# Pontos_Cegos.net
KiCad netlist of a schematic drawn in EAGLE
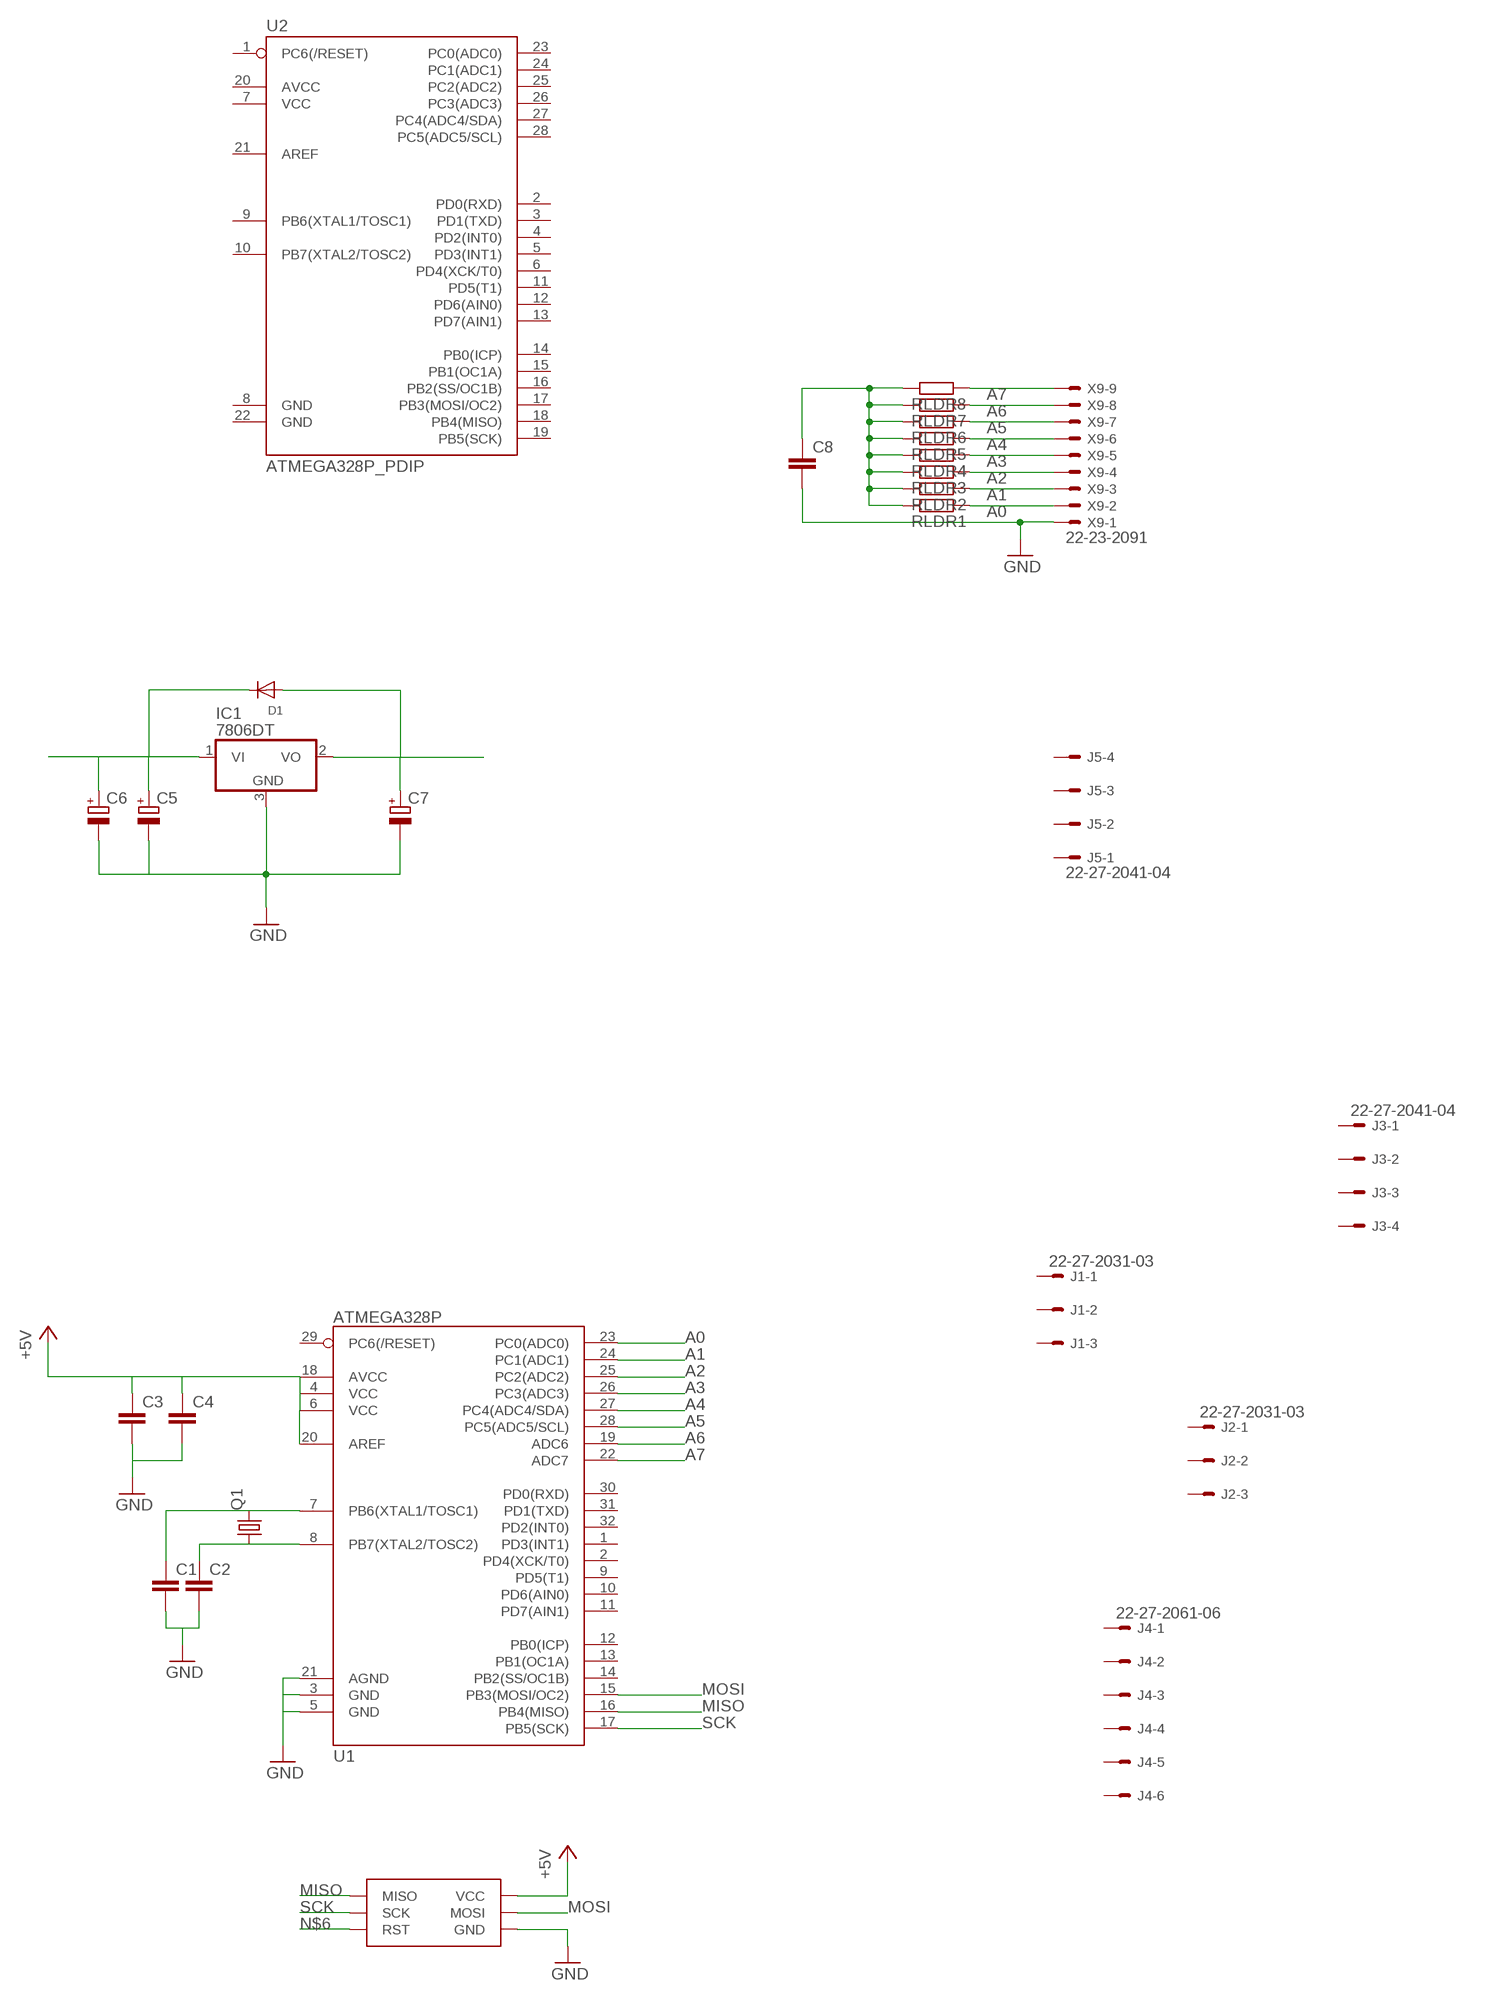
[diagram p0: schematic, sheet 1]

(export (version "E")
  (design (tool "Eeschema 10.0.6"))
  (components
    (comp (ref "C1")
      (value "C-EUC0805")
      (footprint "eagle-import:C0805")
      (libsource (lib "eagle-import") (part "C-EUC0805"))
    )
    (comp (ref "C2")
      (value "C-EUC0805")
      (footprint "eagle-import:C0805")
      (libsource (lib "eagle-import") (part "C-EUC0805"))
    )
    (comp (ref "C3")
      (value "C-EUC0805")
      (footprint "eagle-import:C0805")
      (libsource (lib "eagle-import") (part "C-EUC0805"))
    )
    (comp (ref "C4")
      (value "C-EUC0805")
      (footprint "eagle-import:C0805")
      (libsource (lib "eagle-import") (part "C-EUC0805"))
    )
    (comp (ref "C5")
      (value "CPOL-EUD")
      (footprint "eagle-import:PANASONIC_D")
      (libsource (lib "eagle-import") (part "CPOL-EUD"))
    )
    (comp (ref "C6")
      (value "CPOL-EUD")
      (footprint "eagle-import:PANASONIC_D")
      (libsource (lib "eagle-import") (part "CPOL-EUD"))
    )
    (comp (ref "C7")
      (value "CPOL-EUD")
      (footprint "eagle-import:PANASONIC_D")
      (libsource (lib "eagle-import") (part "CPOL-EUD"))
    )
    (comp (ref "C8")
      (value "C-EUC0805")
      (footprint "eagle-import:C0805")
      (libsource (lib "eagle-import") (part "C-EUC0805"))
    )
    (comp (ref "D1")
      (value "DIODESMA")
      (footprint "eagle-import:SMADIODE")
      (libsource (lib "eagle-import") (part "DIODESMA"))
    )
    (comp (ref "IC1")
      (value "7806DT")
      (footprint "eagle-import:TO252")
      (libsource (lib "eagle-import") (part "78DT06"))
    )
    (comp (ref "J1")
      (value "22-27-2031-03")
      (footprint "eagle-import:6410-03")
      (libsource (lib "eagle-import") (part "22-?-0327-2031"))
    )
    (comp (ref "J2")
      (value "22-27-2031-03")
      (footprint "eagle-import:6410-03")
      (libsource (lib "eagle-import") (part "22-?-0327-2031"))
    )
    (comp (ref "J3")
      (value "22-27-2041-04")
      (footprint "eagle-import:6410-04")
      (libsource (lib "eagle-import") (part "22-?-0427-2041"))
    )
    (comp (ref "J4")
      (value "22-27-2061-06")
      (footprint "eagle-import:6410-06")
      (libsource (lib "eagle-import") (part "22-?-0627-2061"))
    )
    (comp (ref "J5")
      (value "22-27-2041-04")
      (footprint "eagle-import:6410-04")
      (libsource (lib "eagle-import") (part "22-?-0427-2041"))
    )
    (comp (ref "Q1")
      (value "CRYSTALHC49U-V")
      (footprint "eagle-import:HC49U-V")
      (libsource (lib "eagle-import") (part "CRYSTALHC49U-V"))
    )
    (comp (ref "RLDR1")
      (value "R-EU_R0603")
      (footprint "eagle-import:R0603")
      (libsource (lib "eagle-import") (part "R-EU_R0603"))
    )
    (comp (ref "RLDR2")
      (value "R-EU_R0603")
      (footprint "eagle-import:R0603")
      (libsource (lib "eagle-import") (part "R-EU_R0603"))
    )
    (comp (ref "RLDR3")
      (value "R-EU_R0603")
      (footprint "eagle-import:R0603")
      (libsource (lib "eagle-import") (part "R-EU_R0603"))
    )
    (comp (ref "RLDR4")
      (value "R-EU_R0603")
      (footprint "eagle-import:R0603")
      (libsource (lib "eagle-import") (part "R-EU_R0603"))
    )
    (comp (ref "RLDR5")
      (value "R-EU_R0603")
      (footprint "eagle-import:R0603")
      (libsource (lib "eagle-import") (part "R-EU_R0603"))
    )
    (comp (ref "RLDR6")
      (value "R-EU_R0603")
      (footprint "eagle-import:R0603")
      (libsource (lib "eagle-import") (part "R-EU_R0603"))
    )
    (comp (ref "RLDR7")
      (value "R-EU_R0603")
      (footprint "eagle-import:R0603")
      (libsource (lib "eagle-import") (part "R-EU_R0603"))
    )
    (comp (ref "RLDR8")
      (value "R-EU_R0603")
      (footprint "eagle-import:R0603")
      (libsource (lib "eagle-import") (part "R-EU_R0603"))
    )
    (comp (ref "U$1")
      (value "ISP_POGOISP_POGO")
      (footprint "eagle-import:ISP_POGO")
      (libsource (lib "eagle-import") (part "ISP_POGOISP_POGO"))
    )
    (comp (ref "U1")
      (value "ATMEGA328P")
      (footprint "eagle-import:TQFP32-08")
      (libsource (lib "eagle-import") (part "ATMEGA328_SMT"))
    )
    (comp (ref "U2")
      (value "ATMEGA328P_PDIP")
      (footprint "eagle-import:DIL28-3")
      (libsource (lib "eagle-import") (part "ATMEGA328P_PDIP"))
    )
    (comp (ref "X9")
      (value "22-23-2091")
      (footprint "eagle-import:22-23-2091")
      (fields (field (name "MF") "MOLEX"))
      (libsource (lib "eagle-import") (part "22-23-2091"))
    )
  )
  (nets
    (net (code "1") (name "+5V") (class "Default")
      (node (ref "C3") (pin "1") (pinfunction "1_1") (pintype "passive"))
      (node (ref "C4") (pin "1") (pinfunction "1_1") (pintype "passive"))
      (node (ref "C8") (pin "1") (pinfunction "1_1") (pintype "passive"))
      (node (ref "RLDR1") (pin "1") (pinfunction "1_1") (pintype "passive"))
      (node (ref "RLDR2") (pin "1") (pinfunction "1_1") (pintype "passive"))
      (node (ref "RLDR3") (pin "1") (pinfunction "1_1") (pintype "passive"))
      (node (ref "RLDR4") (pin "1") (pinfunction "1_1") (pintype "passive"))
      (node (ref "RLDR5") (pin "1") (pinfunction "1_1") (pintype "passive"))
      (node (ref "RLDR6") (pin "1") (pinfunction "1_1") (pintype "passive"))
      (node (ref "RLDR7") (pin "1") (pinfunction "1_1") (pintype "passive"))
      (node (ref "RLDR8") (pin "1") (pinfunction "1_1") (pintype "passive"))
      (node (ref "U$1") (pin "VCC") (pinfunction "VCC_VCC") (pintype "bidirectional"))
      (node (ref "U1") (pin "18") (pinfunction "AVCC_18") (pintype "bidirectional"))
      (node (ref "U1") (pin "20") (pinfunction "AREF_20") (pintype "bidirectional"))
      (node (ref "U1") (pin "4") (pinfunction "VCC_4") (pintype "bidirectional"))
      (node (ref "U1") (pin "6") (pinfunction "VCC_6") (pintype "bidirectional"))
    )
    (net (code "2") (name "/A0") (class "Default")
      (node (ref "RLDR1") (pin "2") (pinfunction "2_2") (pintype "passive"))
      (node (ref "U1") (pin "23") (pinfunction "PC0(ADC0)_23") (pintype "bidirectional"))
      (node (ref "X9") (pin "2") (pinfunction "S_2") (pintype "passive"))
    )
    (net (code "3") (name "/A1") (class "Default")
      (node (ref "RLDR2") (pin "2") (pinfunction "2_2") (pintype "passive"))
      (node (ref "U1") (pin "24") (pinfunction "PC1(ADC1)_24") (pintype "bidirectional"))
      (node (ref "X9") (pin "3") (pinfunction "S_3") (pintype "passive"))
    )
    (net (code "4") (name "/A2") (class "Default")
      (node (ref "RLDR3") (pin "2") (pinfunction "2_2") (pintype "passive"))
      (node (ref "U1") (pin "25") (pinfunction "PC2(ADC2)_25") (pintype "bidirectional"))
      (node (ref "X9") (pin "4") (pinfunction "S_4") (pintype "passive"))
    )
    (net (code "5") (name "/A3") (class "Default")
      (node (ref "RLDR4") (pin "2") (pinfunction "2_2") (pintype "passive"))
      (node (ref "U1") (pin "26") (pinfunction "PC3(ADC3)_26") (pintype "bidirectional"))
      (node (ref "X9") (pin "5") (pinfunction "S_5") (pintype "passive"))
    )
    (net (code "6") (name "/A4") (class "Default")
      (node (ref "RLDR5") (pin "2") (pinfunction "2_2") (pintype "passive"))
      (node (ref "U1") (pin "27") (pinfunction "PC4(ADC4/SDA)_27") (pintype "bidirectional"))
      (node (ref "X9") (pin "6") (pinfunction "S_6") (pintype "passive"))
    )
    (net (code "7") (name "/A5") (class "Default")
      (node (ref "RLDR6") (pin "2") (pinfunction "2_2") (pintype "passive"))
      (node (ref "U1") (pin "28") (pinfunction "PC5(ADC5/SCL)_28") (pintype "bidirectional"))
      (node (ref "X9") (pin "7") (pinfunction "S_7") (pintype "passive"))
    )
    (net (code "8") (name "/A6") (class "Default")
      (node (ref "RLDR7") (pin "2") (pinfunction "2_2") (pintype "passive"))
      (node (ref "U1") (pin "19") (pinfunction "ADC6_19") (pintype "bidirectional"))
      (node (ref "X9") (pin "8") (pinfunction "S_8") (pintype "passive"))
    )
    (net (code "9") (name "/A7") (class "Default")
      (node (ref "RLDR8") (pin "2") (pinfunction "2_2") (pintype "passive"))
      (node (ref "U1") (pin "22") (pinfunction "ADC7_22") (pintype "bidirectional"))
      (node (ref "X9") (pin "9") (pinfunction "S_9") (pintype "passive"))
    )
    (net (code "10") (name "/MISO") (class "Default")
      (node (ref "U$1") (pin "MISO") (pinfunction "MISO_MISO") (pintype "bidirectional"))
      (node (ref "U1") (pin "16") (pinfunction "PB4(MISO)_16") (pintype "bidirectional"))
    )
    (net (code "11") (name "/MOSI") (class "Default")
      (node (ref "U$1") (pin "MOSI") (pinfunction "MOSI_MOSI") (pintype "bidirectional"))
      (node (ref "U1") (pin "15") (pinfunction "PB3(MOSI/OC2)_15") (pintype "bidirectional"))
    )
    (net (code "12") (name "/N$6") (class "Default")
      (node (ref "U$1") (pin "RST") (pinfunction "RST_RST") (pintype "bidirectional"))
    )
    (net (code "13") (name "/SCK") (class "Default")
      (node (ref "U$1") (pin "SCK") (pinfunction "SCK_SCK") (pintype "bidirectional"))
      (node (ref "U1") (pin "17") (pinfunction "PB5(SCK)_17") (pintype "bidirectional"))
    )
    (net (code "14") (name "GND") (class "Default")
      (node (ref "C1") (pin "2") (pinfunction "2_2") (pintype "passive"))
      (node (ref "C2") (pin "2") (pinfunction "2_2") (pintype "passive"))
      (node (ref "C3") (pin "2") (pinfunction "2_2") (pintype "passive"))
      (node (ref "C4") (pin "2") (pinfunction "2_2") (pintype "passive"))
      (node (ref "C5") (pin "-") (pinfunction "-_-") (pintype "passive"))
      (node (ref "C6") (pin "-") (pinfunction "-_-") (pintype "passive"))
      (node (ref "C7") (pin "-") (pinfunction "-_-") (pintype "passive"))
      (node (ref "C8") (pin "2") (pinfunction "2_2") (pintype "passive"))
      (node (ref "IC1") (pin "3") (pinfunction "GND_3") (pintype "passive"))
      (node (ref "U$1") (pin "GND") (pinfunction "GND_GND") (pintype "bidirectional"))
      (node (ref "U1") (pin "21") (pinfunction "AGND_21") (pintype "bidirectional"))
      (node (ref "U1") (pin "3") (pinfunction "GND_3") (pintype "bidirectional"))
      (node (ref "U1") (pin "5") (pinfunction "GND_5") (pintype "bidirectional"))
      (node (ref "X9") (pin "1") (pinfunction "S_1") (pintype "passive"))
    )
    (net (code "15") (name "Net-(IC1-VI)") (class "Default")
      (node (ref "C5") (pin "+") (pinfunction "+_+") (pintype "passive"))
      (node (ref "C6") (pin "+") (pinfunction "+_+") (pintype "passive"))
      (node (ref "D1") (pin "C") (pinfunction "C_C") (pintype "passive"))
      (node (ref "IC1") (pin "1") (pinfunction "VI_1") (pintype "input"))
    )
    (net (code "16") (name "Net-(IC1-VO)") (class "Default")
      (node (ref "C7") (pin "+") (pinfunction "+_+") (pintype "passive"))
      (node (ref "D1") (pin "A") (pinfunction "A_A") (pintype "passive"))
      (node (ref "IC1") (pin "2") (pinfunction "VO_2") (pintype "passive"))
    )
    (net (code "17") (name "Net-(U1-PB6(XTAL1{slash}TOSC1))") (class "Default")
      (node (ref "C1") (pin "1") (pinfunction "1_1") (pintype "passive"))
      (node (ref "Q1") (pin "2") (pinfunction "2_2") (pintype "passive"))
      (node (ref "U1") (pin "7") (pinfunction "PB6(XTAL1/TOSC1)_7") (pintype "bidirectional"))
    )
    (net (code "18") (name "Net-(U1-PB7(XTAL2{slash}TOSC2))") (class "Default")
      (node (ref "C2") (pin "1") (pinfunction "1_1") (pintype "passive"))
      (node (ref "Q1") (pin "1") (pinfunction "1_1") (pintype "passive"))
      (node (ref "U1") (pin "8") (pinfunction "PB7(XTAL2/TOSC2)_8") (pintype "bidirectional"))
    )
    (net (code "19") (name "unconnected-(J1A-S-Pad1)") (class "Default")
      (node (ref "J1") (pin "1") (pinfunction "S_1") (pintype "passive"))
    )
    (net (code "20") (name "unconnected-(J1B-S-Pad2)") (class "Default")
      (node (ref "J1") (pin "2") (pinfunction "S_2") (pintype "passive"))
    )
    (net (code "21") (name "unconnected-(J1C-S-Pad3)") (class "Default")
      (node (ref "J1") (pin "3") (pinfunction "S_3") (pintype "passive"))
    )
    (net (code "22") (name "unconnected-(J2A-S-Pad1)") (class "Default")
      (node (ref "J2") (pin "1") (pinfunction "S_1") (pintype "passive"))
    )
    (net (code "23") (name "unconnected-(J2B-S-Pad2)") (class "Default")
      (node (ref "J2") (pin "2") (pinfunction "S_2") (pintype "passive"))
    )
    (net (code "24") (name "unconnected-(J2C-S-Pad3)") (class "Default")
      (node (ref "J2") (pin "3") (pinfunction "S_3") (pintype "passive"))
    )
    (net (code "25") (name "unconnected-(J3A-S-Pad1)") (class "Default")
      (node (ref "J3") (pin "1") (pinfunction "S_1") (pintype "passive"))
    )
    (net (code "26") (name "unconnected-(J3B-S-Pad2)") (class "Default")
      (node (ref "J3") (pin "2") (pinfunction "S_2") (pintype "passive"))
    )
    (net (code "27") (name "unconnected-(J3C-S-Pad3)") (class "Default")
      (node (ref "J3") (pin "3") (pinfunction "S_3") (pintype "passive"))
    )
    (net (code "28") (name "unconnected-(J3D-S-Pad4)") (class "Default")
      (node (ref "J3") (pin "4") (pinfunction "S_4") (pintype "passive"))
    )
    (net (code "29") (name "unconnected-(J4A-S-Pad1)") (class "Default")
      (node (ref "J4") (pin "1") (pinfunction "S_1") (pintype "passive"))
    )
    (net (code "30") (name "unconnected-(J4B-S-Pad2)") (class "Default")
      (node (ref "J4") (pin "2") (pinfunction "S_2") (pintype "passive"))
    )
    (net (code "31") (name "unconnected-(J4C-S-Pad3)") (class "Default")
      (node (ref "J4") (pin "3") (pinfunction "S_3") (pintype "passive"))
    )
    (net (code "32") (name "unconnected-(J4D-S-Pad4)") (class "Default")
      (node (ref "J4") (pin "4") (pinfunction "S_4") (pintype "passive"))
    )
    (net (code "33") (name "unconnected-(J4E-S-Pad5)") (class "Default")
      (node (ref "J4") (pin "5") (pinfunction "S_5") (pintype "passive"))
    )
    (net (code "34") (name "unconnected-(J4F-S-Pad6)") (class "Default")
      (node (ref "J4") (pin "6") (pinfunction "S_6") (pintype "passive"))
    )
    (net (code "35") (name "unconnected-(J5A-S-Pad1)") (class "Default")
      (node (ref "J5") (pin "1") (pinfunction "S_1") (pintype "passive"))
    )
    (net (code "36") (name "unconnected-(J5B-S-Pad2)") (class "Default")
      (node (ref "J5") (pin "2") (pinfunction "S_2") (pintype "passive"))
    )
    (net (code "37") (name "unconnected-(J5C-S-Pad3)") (class "Default")
      (node (ref "J5") (pin "3") (pinfunction "S_3") (pintype "passive"))
    )
    (net (code "38") (name "unconnected-(J5D-S-Pad4)") (class "Default")
      (node (ref "J5") (pin "4") (pinfunction "S_4") (pintype "passive"))
    )
    (net (code "39") (name "unconnected-(U1-PB0(ICP)-Pad12)") (class "Default")
      (node (ref "U1") (pin "12") (pinfunction "PB0(ICP)_12") (pintype "bidirectional"))
    )
    (net (code "40") (name "unconnected-(U1-PB1(OC1A)-Pad13)") (class "Default")
      (node (ref "U1") (pin "13") (pinfunction "PB1(OC1A)_13") (pintype "bidirectional"))
    )
    (net (code "41") (name "unconnected-(U1-PB2(SS{slash}OC1B)-Pad14)") (class "Default")
      (node (ref "U1") (pin "14") (pinfunction "PB2(SS/OC1B)_14") (pintype "bidirectional"))
    )
    (net (code "42") (name "unconnected-(U1-PC6({slash}RESET)-Pad29)") (class "Default")
      (node (ref "U1") (pin "29") (pinfunction "PC6(/RESET)_29") (pintype "bidirectional"))
    )
    (net (code "43") (name "unconnected-(U1-PD0(RXD)-Pad30)") (class "Default")
      (node (ref "U1") (pin "30") (pinfunction "PD0(RXD)_30") (pintype "bidirectional"))
    )
    (net (code "44") (name "unconnected-(U1-PD1(TXD)-Pad31)") (class "Default")
      (node (ref "U1") (pin "31") (pinfunction "PD1(TXD)_31") (pintype "bidirectional"))
    )
    (net (code "45") (name "unconnected-(U1-PD2(INT0)-Pad32)") (class "Default")
      (node (ref "U1") (pin "32") (pinfunction "PD2(INT0)_32") (pintype "bidirectional"))
    )
    (net (code "46") (name "unconnected-(U1-PD3(INT1)-Pad1)") (class "Default")
      (node (ref "U1") (pin "1") (pinfunction "PD3(INT1)_1") (pintype "bidirectional"))
    )
    (net (code "47") (name "unconnected-(U1-PD4(XCK{slash}T0)-Pad2)") (class "Default")
      (node (ref "U1") (pin "2") (pinfunction "PD4(XCK/T0)_2") (pintype "bidirectional"))
    )
    (net (code "48") (name "unconnected-(U1-PD5(T1)-Pad9)") (class "Default")
      (node (ref "U1") (pin "9") (pinfunction "PD5(T1)_9") (pintype "bidirectional"))
    )
    (net (code "49") (name "unconnected-(U1-PD6(AIN0)-Pad10)") (class "Default")
      (node (ref "U1") (pin "10") (pinfunction "PD6(AIN0)_10") (pintype "bidirectional"))
    )
    (net (code "50") (name "unconnected-(U1-PD7(AIN1)-Pad11)") (class "Default")
      (node (ref "U1") (pin "11") (pinfunction "PD7(AIN1)_11") (pintype "bidirectional"))
    )
    (net (code "51") (name "unconnected-(U2-AREF-Pad21)") (class "Default")
      (node (ref "U2") (pin "21") (pinfunction "AREF_21") (pintype "bidirectional"))
    )
    (net (code "52") (name "unconnected-(U2-AVCC-Pad20)") (class "Default")
      (node (ref "U2") (pin "20") (pinfunction "AVCC_20") (pintype "bidirectional"))
    )
    (net (code "53") (name "unconnected-(U2-GND-Pad8)") (class "Default")
      (node (ref "U2") (pin "8") (pinfunction "GND_8") (pintype "bidirectional"))
    )
    (net (code "54") (name "unconnected-(U2-GND-Pad22)") (class "Default")
      (node (ref "U2") (pin "22") (pinfunction "GND_22") (pintype "bidirectional"))
    )
    (net (code "55") (name "unconnected-(U2-PB0(ICP)-Pad14)") (class "Default")
      (node (ref "U2") (pin "14") (pinfunction "PB0(ICP)_14") (pintype "bidirectional"))
    )
    (net (code "56") (name "unconnected-(U2-PB1(OC1A)-Pad15)") (class "Default")
      (node (ref "U2") (pin "15") (pinfunction "PB1(OC1A)_15") (pintype "bidirectional"))
    )
    (net (code "57") (name "unconnected-(U2-PB2(SS{slash}OC1B)-Pad16)") (class "Default")
      (node (ref "U2") (pin "16") (pinfunction "PB2(SS/OC1B)_16") (pintype "bidirectional"))
    )
    (net (code "58") (name "unconnected-(U2-PB3(MOSI{slash}OC2)-Pad17)") (class "Default")
      (node (ref "U2") (pin "17") (pinfunction "PB3(MOSI/OC2)_17") (pintype "bidirectional"))
    )
    (net (code "59") (name "unconnected-(U2-PB4(MISO)-Pad18)") (class "Default")
      (node (ref "U2") (pin "18") (pinfunction "PB4(MISO)_18") (pintype "bidirectional"))
    )
    (net (code "60") (name "unconnected-(U2-PB5(SCK)-Pad19)") (class "Default")
      (node (ref "U2") (pin "19") (pinfunction "PB5(SCK)_19") (pintype "bidirectional"))
    )
    (net (code "61") (name "unconnected-(U2-PB6(XTAL1{slash}TOSC1)-Pad9)") (class "Default")
      (node (ref "U2") (pin "9") (pinfunction "PB6(XTAL1/TOSC1)_9") (pintype "bidirectional"))
    )
    (net (code "62") (name "unconnected-(U2-PB7(XTAL2{slash}TOSC2)-Pad10)") (class "Default")
      (node (ref "U2") (pin "10") (pinfunction "PB7(XTAL2/TOSC2)_10") (pintype "bidirectional"))
    )
    (net (code "63") (name "unconnected-(U2-PC0(ADC0)-Pad23)") (class "Default")
      (node (ref "U2") (pin "23") (pinfunction "PC0(ADC0)_23") (pintype "bidirectional"))
    )
    (net (code "64") (name "unconnected-(U2-PC1(ADC1)-Pad24)") (class "Default")
      (node (ref "U2") (pin "24") (pinfunction "PC1(ADC1)_24") (pintype "bidirectional"))
    )
    (net (code "65") (name "unconnected-(U2-PC2(ADC2)-Pad25)") (class "Default")
      (node (ref "U2") (pin "25") (pinfunction "PC2(ADC2)_25") (pintype "bidirectional"))
    )
    (net (code "66") (name "unconnected-(U2-PC3(ADC3)-Pad26)") (class "Default")
      (node (ref "U2") (pin "26") (pinfunction "PC3(ADC3)_26") (pintype "bidirectional"))
    )
    (net (code "67") (name "unconnected-(U2-PC4(ADC4{slash}SDA)-Pad27)") (class "Default")
      (node (ref "U2") (pin "27") (pinfunction "PC4(ADC4/SDA)_27") (pintype "bidirectional"))
    )
    (net (code "68") (name "unconnected-(U2-PC5(ADC5{slash}SCL)-Pad28)") (class "Default")
      (node (ref "U2") (pin "28") (pinfunction "PC5(ADC5/SCL)_28") (pintype "bidirectional"))
    )
    (net (code "69") (name "unconnected-(U2-PC6({slash}RESET)-Pad1)") (class "Default")
      (node (ref "U2") (pin "1") (pinfunction "PC6(/RESET)_1") (pintype "bidirectional"))
    )
    (net (code "70") (name "unconnected-(U2-PD0(RXD)-Pad2)") (class "Default")
      (node (ref "U2") (pin "2") (pinfunction "PD0(RXD)_2") (pintype "bidirectional"))
    )
    (net (code "71") (name "unconnected-(U2-PD1(TXD)-Pad3)") (class "Default")
      (node (ref "U2") (pin "3") (pinfunction "PD1(TXD)_3") (pintype "bidirectional"))
    )
    (net (code "72") (name "unconnected-(U2-PD2(INT0)-Pad4)") (class "Default")
      (node (ref "U2") (pin "4") (pinfunction "PD2(INT0)_4") (pintype "bidirectional"))
    )
    (net (code "73") (name "unconnected-(U2-PD3(INT1)-Pad5)") (class "Default")
      (node (ref "U2") (pin "5") (pinfunction "PD3(INT1)_5") (pintype "bidirectional"))
    )
    (net (code "74") (name "unconnected-(U2-PD4(XCK{slash}T0)-Pad6)") (class "Default")
      (node (ref "U2") (pin "6") (pinfunction "PD4(XCK/T0)_6") (pintype "bidirectional"))
    )
    (net (code "75") (name "unconnected-(U2-PD5(T1)-Pad11)") (class "Default")
      (node (ref "U2") (pin "11") (pinfunction "PD5(T1)_11") (pintype "bidirectional"))
    )
    (net (code "76") (name "unconnected-(U2-PD6(AIN0)-Pad12)") (class "Default")
      (node (ref "U2") (pin "12") (pinfunction "PD6(AIN0)_12") (pintype "bidirectional"))
    )
    (net (code "77") (name "unconnected-(U2-PD7(AIN1)-Pad13)") (class "Default")
      (node (ref "U2") (pin "13") (pinfunction "PD7(AIN1)_13") (pintype "bidirectional"))
    )
    (net (code "78") (name "unconnected-(U2-VCC-Pad7)") (class "Default")
      (node (ref "U2") (pin "7") (pinfunction "VCC_7") (pintype "bidirectional"))
    )
  )
)
